# Sheet2.net
KiCad netlist of a schematic drawn in Altium Designer
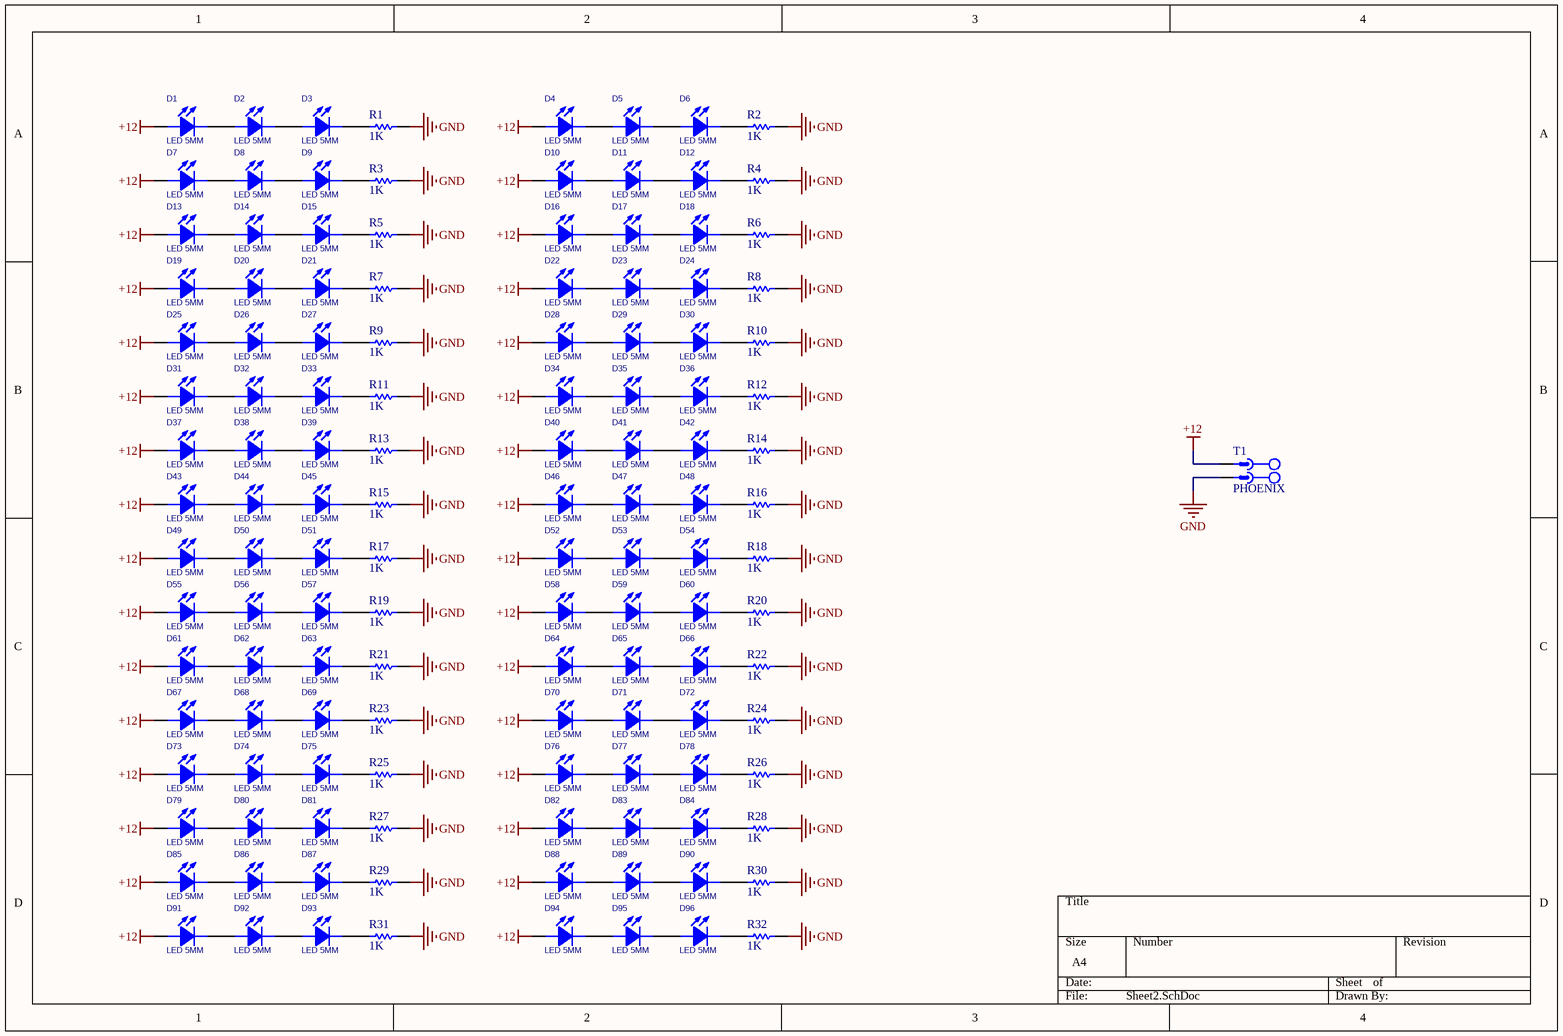
[diagram p0: Sheet2.SchDoc]

(export (version "E")
  (design (tool "Eeschema 10.0.6"))
  (components
    (comp (ref "D1")
      (value "LED 5MM")
      (footprint "LED5MM_BLUE")
      (description "Light Emitting Diode")
      (fields (field (name "DESIGNER") "Abbas Basereh"))
      (libsource (lib "Altium") (part "LED 5MM"))
    )
    (comp (ref "D2")
      (value "LED 5MM")
      (footprint "LED5MM_BLUE")
      (description "Light Emitting Diode")
      (fields (field (name "DESIGNER") "Abbas Basereh"))
      (libsource (lib "Altium") (part "LED 5MM"))
    )
    (comp (ref "D3")
      (value "LED 5MM")
      (footprint "LED5MM_BLUE")
      (description "Light Emitting Diode")
      (fields (field (name "DESIGNER") "Abbas Basereh"))
      (libsource (lib "Altium") (part "LED 5MM"))
    )
    (comp (ref "D4")
      (value "LED 5MM")
      (footprint "LED5MM_BLUE")
      (description "Light Emitting Diode")
      (fields (field (name "DESIGNER") "Abbas Basereh"))
      (libsource (lib "Altium") (part "LED 5MM"))
    )
    (comp (ref "D5")
      (value "LED 5MM")
      (footprint "LED5MM_BLUE")
      (description "Light Emitting Diode")
      (fields (field (name "DESIGNER") "Abbas Basereh"))
      (libsource (lib "Altium") (part "LED 5MM"))
    )
    (comp (ref "D6")
      (value "LED 5MM")
      (footprint "LED5MM_BLUE")
      (description "Light Emitting Diode")
      (fields (field (name "DESIGNER") "Abbas Basereh"))
      (libsource (lib "Altium") (part "LED 5MM"))
    )
    (comp (ref "D7")
      (value "LED 5MM")
      (footprint "LED5MM_BLUE")
      (description "Light Emitting Diode")
      (fields (field (name "DESIGNER") "Abbas Basereh"))
      (libsource (lib "Altium") (part "LED 5MM"))
    )
    (comp (ref "D8")
      (value "LED 5MM")
      (footprint "LED5MM_BLUE")
      (description "Light Emitting Diode")
      (fields (field (name "DESIGNER") "Abbas Basereh"))
      (libsource (lib "Altium") (part "LED 5MM"))
    )
    (comp (ref "D9")
      (value "LED 5MM")
      (footprint "LED5MM_BLUE")
      (description "Light Emitting Diode")
      (fields (field (name "DESIGNER") "Abbas Basereh"))
      (libsource (lib "Altium") (part "LED 5MM"))
    )
    (comp (ref "D10")
      (value "LED 5MM")
      (footprint "LED5MM_BLUE")
      (description "Light Emitting Diode")
      (fields (field (name "DESIGNER") "Abbas Basereh"))
      (libsource (lib "Altium") (part "LED 5MM"))
    )
    (comp (ref "D11")
      (value "LED 5MM")
      (footprint "LED5MM_BLUE")
      (description "Light Emitting Diode")
      (fields (field (name "DESIGNER") "Abbas Basereh"))
      (libsource (lib "Altium") (part "LED 5MM"))
    )
    (comp (ref "D12")
      (value "LED 5MM")
      (footprint "LED5MM_BLUE")
      (description "Light Emitting Diode")
      (fields (field (name "DESIGNER") "Abbas Basereh"))
      (libsource (lib "Altium") (part "LED 5MM"))
    )
    (comp (ref "D13")
      (value "LED 5MM")
      (footprint "LED5MM_BLUE")
      (description "Light Emitting Diode")
      (fields (field (name "DESIGNER") "Abbas Basereh"))
      (libsource (lib "Altium") (part "LED 5MM"))
    )
    (comp (ref "D14")
      (value "LED 5MM")
      (footprint "LED5MM_BLUE")
      (description "Light Emitting Diode")
      (fields (field (name "DESIGNER") "Abbas Basereh"))
      (libsource (lib "Altium") (part "LED 5MM"))
    )
    (comp (ref "D15")
      (value "LED 5MM")
      (footprint "LED5MM_BLUE")
      (description "Light Emitting Diode")
      (fields (field (name "DESIGNER") "Abbas Basereh"))
      (libsource (lib "Altium") (part "LED 5MM"))
    )
    (comp (ref "D16")
      (value "LED 5MM")
      (footprint "LED5MM_BLUE")
      (description "Light Emitting Diode")
      (fields (field (name "DESIGNER") "Abbas Basereh"))
      (libsource (lib "Altium") (part "LED 5MM"))
    )
    (comp (ref "D17")
      (value "LED 5MM")
      (footprint "LED5MM_BLUE")
      (description "Light Emitting Diode")
      (fields (field (name "DESIGNER") "Abbas Basereh"))
      (libsource (lib "Altium") (part "LED 5MM"))
    )
    (comp (ref "D18")
      (value "LED 5MM")
      (footprint "LED5MM_BLUE")
      (description "Light Emitting Diode")
      (fields (field (name "DESIGNER") "Abbas Basereh"))
      (libsource (lib "Altium") (part "LED 5MM"))
    )
    (comp (ref "D19")
      (value "LED 5MM")
      (footprint "LED5MM_BLUE")
      (description "Light Emitting Diode")
      (fields (field (name "DESIGNER") "Abbas Basereh"))
      (libsource (lib "Altium") (part "LED 5MM"))
    )
    (comp (ref "D20")
      (value "LED 5MM")
      (footprint "LED5MM_BLUE")
      (description "Light Emitting Diode")
      (fields (field (name "DESIGNER") "Abbas Basereh"))
      (libsource (lib "Altium") (part "LED 5MM"))
    )
    (comp (ref "D21")
      (value "LED 5MM")
      (footprint "LED5MM_BLUE")
      (description "Light Emitting Diode")
      (fields (field (name "DESIGNER") "Abbas Basereh"))
      (libsource (lib "Altium") (part "LED 5MM"))
    )
    (comp (ref "D22")
      (value "LED 5MM")
      (footprint "LED5MM_BLUE")
      (description "Light Emitting Diode")
      (fields (field (name "DESIGNER") "Abbas Basereh"))
      (libsource (lib "Altium") (part "LED 5MM"))
    )
    (comp (ref "D23")
      (value "LED 5MM")
      (footprint "LED5MM_BLUE")
      (description "Light Emitting Diode")
      (fields (field (name "DESIGNER") "Abbas Basereh"))
      (libsource (lib "Altium") (part "LED 5MM"))
    )
    (comp (ref "D24")
      (value "LED 5MM")
      (footprint "LED5MM_BLUE")
      (description "Light Emitting Diode")
      (fields (field (name "DESIGNER") "Abbas Basereh"))
      (libsource (lib "Altium") (part "LED 5MM"))
    )
    (comp (ref "D25")
      (value "LED 5MM")
      (footprint "LED5MM_BLUE")
      (description "Light Emitting Diode")
      (fields (field (name "DESIGNER") "Abbas Basereh"))
      (libsource (lib "Altium") (part "LED 5MM"))
    )
    (comp (ref "D26")
      (value "LED 5MM")
      (footprint "LED5MM_BLUE")
      (description "Light Emitting Diode")
      (fields (field (name "DESIGNER") "Abbas Basereh"))
      (libsource (lib "Altium") (part "LED 5MM"))
    )
    (comp (ref "D27")
      (value "LED 5MM")
      (footprint "LED5MM_BLUE")
      (description "Light Emitting Diode")
      (fields (field (name "DESIGNER") "Abbas Basereh"))
      (libsource (lib "Altium") (part "LED 5MM"))
    )
    (comp (ref "D28")
      (value "LED 5MM")
      (footprint "LED5MM_BLUE")
      (description "Light Emitting Diode")
      (fields (field (name "DESIGNER") "Abbas Basereh"))
      (libsource (lib "Altium") (part "LED 5MM"))
    )
    (comp (ref "D29")
      (value "LED 5MM")
      (footprint "LED5MM_BLUE")
      (description "Light Emitting Diode")
      (fields (field (name "DESIGNER") "Abbas Basereh"))
      (libsource (lib "Altium") (part "LED 5MM"))
    )
    (comp (ref "D30")
      (value "LED 5MM")
      (footprint "LED5MM_BLUE")
      (description "Light Emitting Diode")
      (fields (field (name "DESIGNER") "Abbas Basereh"))
      (libsource (lib "Altium") (part "LED 5MM"))
    )
    (comp (ref "D31")
      (value "LED 5MM")
      (footprint "LED5MM_BLUE")
      (description "Light Emitting Diode")
      (fields (field (name "DESIGNER") "Abbas Basereh"))
      (libsource (lib "Altium") (part "LED 5MM"))
    )
    (comp (ref "D32")
      (value "LED 5MM")
      (footprint "LED5MM_BLUE")
      (description "Light Emitting Diode")
      (fields (field (name "DESIGNER") "Abbas Basereh"))
      (libsource (lib "Altium") (part "LED 5MM"))
    )
    (comp (ref "D33")
      (value "LED 5MM")
      (footprint "LED5MM_BLUE")
      (description "Light Emitting Diode")
      (fields (field (name "DESIGNER") "Abbas Basereh"))
      (libsource (lib "Altium") (part "LED 5MM"))
    )
    (comp (ref "D34")
      (value "LED 5MM")
      (footprint "LED5MM_BLUE")
      (description "Light Emitting Diode")
      (fields (field (name "DESIGNER") "Abbas Basereh"))
      (libsource (lib "Altium") (part "LED 5MM"))
    )
    (comp (ref "D35")
      (value "LED 5MM")
      (footprint "LED5MM_BLUE")
      (description "Light Emitting Diode")
      (fields (field (name "DESIGNER") "Abbas Basereh"))
      (libsource (lib "Altium") (part "LED 5MM"))
    )
    (comp (ref "D36")
      (value "LED 5MM")
      (footprint "LED5MM_BLUE")
      (description "Light Emitting Diode")
      (fields (field (name "DESIGNER") "Abbas Basereh"))
      (libsource (lib "Altium") (part "LED 5MM"))
    )
    (comp (ref "D37")
      (value "LED 5MM")
      (footprint "LED5MM_BLUE")
      (description "Light Emitting Diode")
      (fields (field (name "DESIGNER") "Abbas Basereh"))
      (libsource (lib "Altium") (part "LED 5MM"))
    )
    (comp (ref "D38")
      (value "LED 5MM")
      (footprint "LED5MM_BLUE")
      (description "Light Emitting Diode")
      (fields (field (name "DESIGNER") "Abbas Basereh"))
      (libsource (lib "Altium") (part "LED 5MM"))
    )
    (comp (ref "D39")
      (value "LED 5MM")
      (footprint "LED5MM_BLUE")
      (description "Light Emitting Diode")
      (fields (field (name "DESIGNER") "Abbas Basereh"))
      (libsource (lib "Altium") (part "LED 5MM"))
    )
    (comp (ref "D40")
      (value "LED 5MM")
      (footprint "LED5MM_BLUE")
      (description "Light Emitting Diode")
      (fields (field (name "DESIGNER") "Abbas Basereh"))
      (libsource (lib "Altium") (part "LED 5MM"))
    )
    (comp (ref "D41")
      (value "LED 5MM")
      (footprint "LED5MM_BLUE")
      (description "Light Emitting Diode")
      (fields (field (name "DESIGNER") "Abbas Basereh"))
      (libsource (lib "Altium") (part "LED 5MM"))
    )
    (comp (ref "D42")
      (value "LED 5MM")
      (footprint "LED5MM_BLUE")
      (description "Light Emitting Diode")
      (fields (field (name "DESIGNER") "Abbas Basereh"))
      (libsource (lib "Altium") (part "LED 5MM"))
    )
    (comp (ref "D43")
      (value "LED 5MM")
      (footprint "LED5MM_BLUE")
      (description "Light Emitting Diode")
      (fields (field (name "DESIGNER") "Abbas Basereh"))
      (libsource (lib "Altium") (part "LED 5MM"))
    )
    (comp (ref "D44")
      (value "LED 5MM")
      (footprint "LED5MM_BLUE")
      (description "Light Emitting Diode")
      (fields (field (name "DESIGNER") "Abbas Basereh"))
      (libsource (lib "Altium") (part "LED 5MM"))
    )
    (comp (ref "D45")
      (value "LED 5MM")
      (footprint "LED5MM_BLUE")
      (description "Light Emitting Diode")
      (fields (field (name "DESIGNER") "Abbas Basereh"))
      (libsource (lib "Altium") (part "LED 5MM"))
    )
    (comp (ref "D46")
      (value "LED 5MM")
      (footprint "LED5MM_BLUE")
      (description "Light Emitting Diode")
      (fields (field (name "DESIGNER") "Abbas Basereh"))
      (libsource (lib "Altium") (part "LED 5MM"))
    )
    (comp (ref "D47")
      (value "LED 5MM")
      (footprint "LED5MM_BLUE")
      (description "Light Emitting Diode")
      (fields (field (name "DESIGNER") "Abbas Basereh"))
      (libsource (lib "Altium") (part "LED 5MM"))
    )
    (comp (ref "D48")
      (value "LED 5MM")
      (footprint "LED5MM_BLUE")
      (description "Light Emitting Diode")
      (fields (field (name "DESIGNER") "Abbas Basereh"))
      (libsource (lib "Altium") (part "LED 5MM"))
    )
    (comp (ref "D49")
      (value "LED 5MM")
      (footprint "LED5MM_BLUE")
      (description "Light Emitting Diode")
      (fields (field (name "DESIGNER") "Abbas Basereh"))
      (libsource (lib "Altium") (part "LED 5MM"))
    )
    (comp (ref "D50")
      (value "LED 5MM")
      (footprint "LED5MM_BLUE")
      (description "Light Emitting Diode")
      (fields (field (name "DESIGNER") "Abbas Basereh"))
      (libsource (lib "Altium") (part "LED 5MM"))
    )
    (comp (ref "D51")
      (value "LED 5MM")
      (footprint "LED5MM_BLUE")
      (description "Light Emitting Diode")
      (fields (field (name "DESIGNER") "Abbas Basereh"))
      (libsource (lib "Altium") (part "LED 5MM"))
    )
    (comp (ref "D52")
      (value "LED 5MM")
      (footprint "LED5MM_BLUE")
      (description "Light Emitting Diode")
      (fields (field (name "DESIGNER") "Abbas Basereh"))
      (libsource (lib "Altium") (part "LED 5MM"))
    )
    (comp (ref "D53")
      (value "LED 5MM")
      (footprint "LED5MM_BLUE")
      (description "Light Emitting Diode")
      (fields (field (name "DESIGNER") "Abbas Basereh"))
      (libsource (lib "Altium") (part "LED 5MM"))
    )
    (comp (ref "D54")
      (value "LED 5MM")
      (footprint "LED5MM_BLUE")
      (description "Light Emitting Diode")
      (fields (field (name "DESIGNER") "Abbas Basereh"))
      (libsource (lib "Altium") (part "LED 5MM"))
    )
    (comp (ref "D55")
      (value "LED 5MM")
      (footprint "LED5MM_BLUE")
      (description "Light Emitting Diode")
      (fields (field (name "DESIGNER") "Abbas Basereh"))
      (libsource (lib "Altium") (part "LED 5MM"))
    )
    (comp (ref "D56")
      (value "LED 5MM")
      (footprint "LED5MM_BLUE")
      (description "Light Emitting Diode")
      (fields (field (name "DESIGNER") "Abbas Basereh"))
      (libsource (lib "Altium") (part "LED 5MM"))
    )
    (comp (ref "D57")
      (value "LED 5MM")
      (footprint "LED5MM_BLUE")
      (description "Light Emitting Diode")
      (fields (field (name "DESIGNER") "Abbas Basereh"))
      (libsource (lib "Altium") (part "LED 5MM"))
    )
    (comp (ref "D58")
      (value "LED 5MM")
      (footprint "LED5MM_BLUE")
      (description "Light Emitting Diode")
      (fields (field (name "DESIGNER") "Abbas Basereh"))
      (libsource (lib "Altium") (part "LED 5MM"))
    )
    (comp (ref "D59")
      (value "LED 5MM")
      (footprint "LED5MM_BLUE")
      (description "Light Emitting Diode")
      (fields (field (name "DESIGNER") "Abbas Basereh"))
      (libsource (lib "Altium") (part "LED 5MM"))
    )
    (comp (ref "D60")
      (value "LED 5MM")
      (footprint "LED5MM_BLUE")
      (description "Light Emitting Diode")
      (fields (field (name "DESIGNER") "Abbas Basereh"))
      (libsource (lib "Altium") (part "LED 5MM"))
    )
    (comp (ref "D61")
      (value "LED 5MM")
      (footprint "LED5MM_BLUE")
      (description "Light Emitting Diode")
      (fields (field (name "DESIGNER") "Abbas Basereh"))
      (libsource (lib "Altium") (part "LED 5MM"))
    )
    (comp (ref "D62")
      (value "LED 5MM")
      (footprint "LED5MM_BLUE")
      (description "Light Emitting Diode")
      (fields (field (name "DESIGNER") "Abbas Basereh"))
      (libsource (lib "Altium") (part "LED 5MM"))
    )
    (comp (ref "D63")
      (value "LED 5MM")
      (footprint "LED5MM_BLUE")
      (description "Light Emitting Diode")
      (fields (field (name "DESIGNER") "Abbas Basereh"))
      (libsource (lib "Altium") (part "LED 5MM"))
    )
    (comp (ref "D64")
      (value "LED 5MM")
      (footprint "LED5MM_BLUE")
      (description "Light Emitting Diode")
      (fields (field (name "DESIGNER") "Abbas Basereh"))
      (libsource (lib "Altium") (part "LED 5MM"))
    )
    (comp (ref "D65")
      (value "LED 5MM")
      (footprint "LED5MM_BLUE")
      (description "Light Emitting Diode")
      (fields (field (name "DESIGNER") "Abbas Basereh"))
      (libsource (lib "Altium") (part "LED 5MM"))
    )
    (comp (ref "D66")
      (value "LED 5MM")
      (footprint "LED5MM_BLUE")
      (description "Light Emitting Diode")
      (fields (field (name "DESIGNER") "Abbas Basereh"))
      (libsource (lib "Altium") (part "LED 5MM"))
    )
    (comp (ref "D67")
      (value "LED 5MM")
      (footprint "LED5MM_BLUE")
      (description "Light Emitting Diode")
      (fields (field (name "DESIGNER") "Abbas Basereh"))
      (libsource (lib "Altium") (part "LED 5MM"))
    )
    (comp (ref "D68")
      (value "LED 5MM")
      (footprint "LED5MM_BLUE")
      (description "Light Emitting Diode")
      (fields (field (name "DESIGNER") "Abbas Basereh"))
      (libsource (lib "Altium") (part "LED 5MM"))
    )
    (comp (ref "D69")
      (value "LED 5MM")
      (footprint "LED5MM_BLUE")
      (description "Light Emitting Diode")
      (fields (field (name "DESIGNER") "Abbas Basereh"))
      (libsource (lib "Altium") (part "LED 5MM"))
    )
    (comp (ref "D70")
      (value "LED 5MM")
      (footprint "LED5MM_BLUE")
      (description "Light Emitting Diode")
      (fields (field (name "DESIGNER") "Abbas Basereh"))
      (libsource (lib "Altium") (part "LED 5MM"))
    )
    (comp (ref "D71")
      (value "LED 5MM")
      (footprint "LED5MM_BLUE")
      (description "Light Emitting Diode")
      (fields (field (name "DESIGNER") "Abbas Basereh"))
      (libsource (lib "Altium") (part "LED 5MM"))
    )
    (comp (ref "D72")
      (value "LED 5MM")
      (footprint "LED5MM_BLUE")
      (description "Light Emitting Diode")
      (fields (field (name "DESIGNER") "Abbas Basereh"))
      (libsource (lib "Altium") (part "LED 5MM"))
    )
    (comp (ref "D73")
      (value "LED 5MM")
      (footprint "LED5MM_BLUE")
      (description "Light Emitting Diode")
      (fields (field (name "DESIGNER") "Abbas Basereh"))
      (libsource (lib "Altium") (part "LED 5MM"))
    )
    (comp (ref "D74")
      (value "LED 5MM")
      (footprint "LED5MM_BLUE")
      (description "Light Emitting Diode")
      (fields (field (name "DESIGNER") "Abbas Basereh"))
      (libsource (lib "Altium") (part "LED 5MM"))
    )
    (comp (ref "D75")
      (value "LED 5MM")
      (footprint "LED5MM_BLUE")
      (description "Light Emitting Diode")
      (fields (field (name "DESIGNER") "Abbas Basereh"))
      (libsource (lib "Altium") (part "LED 5MM"))
    )
    (comp (ref "D76")
      (value "LED 5MM")
      (footprint "LED5MM_BLUE")
      (description "Light Emitting Diode")
      (fields (field (name "DESIGNER") "Abbas Basereh"))
      (libsource (lib "Altium") (part "LED 5MM"))
    )
    (comp (ref "D77")
      (value "LED 5MM")
      (footprint "LED5MM_BLUE")
      (description "Light Emitting Diode")
      (fields (field (name "DESIGNER") "Abbas Basereh"))
      (libsource (lib "Altium") (part "LED 5MM"))
    )
    (comp (ref "D78")
      (value "LED 5MM")
      (footprint "LED5MM_BLUE")
      (description "Light Emitting Diode")
      (fields (field (name "DESIGNER") "Abbas Basereh"))
      (libsource (lib "Altium") (part "LED 5MM"))
    )
    (comp (ref "D79")
      (value "LED 5MM")
      (footprint "LED5MM_BLUE")
      (description "Light Emitting Diode")
      (fields (field (name "DESIGNER") "Abbas Basereh"))
      (libsource (lib "Altium") (part "LED 5MM"))
    )
    (comp (ref "D80")
      (value "LED 5MM")
      (footprint "LED5MM_BLUE")
      (description "Light Emitting Diode")
      (fields (field (name "DESIGNER") "Abbas Basereh"))
      (libsource (lib "Altium") (part "LED 5MM"))
    )
    (comp (ref "D81")
      (value "LED 5MM")
      (footprint "LED5MM_BLUE")
      (description "Light Emitting Diode")
      (fields (field (name "DESIGNER") "Abbas Basereh"))
      (libsource (lib "Altium") (part "LED 5MM"))
    )
    (comp (ref "D82")
      (value "LED 5MM")
      (footprint "LED5MM_BLUE")
      (description "Light Emitting Diode")
      (fields (field (name "DESIGNER") "Abbas Basereh"))
      (libsource (lib "Altium") (part "LED 5MM"))
    )
    (comp (ref "D83")
      (value "LED 5MM")
      (footprint "LED5MM_BLUE")
      (description "Light Emitting Diode")
      (fields (field (name "DESIGNER") "Abbas Basereh"))
      (libsource (lib "Altium") (part "LED 5MM"))
    )
    (comp (ref "D84")
      (value "LED 5MM")
      (footprint "LED5MM_BLUE")
      (description "Light Emitting Diode")
      (fields (field (name "DESIGNER") "Abbas Basereh"))
      (libsource (lib "Altium") (part "LED 5MM"))
    )
    (comp (ref "D85")
      (value "LED 5MM")
      (footprint "LED5MM_BLUE")
      (description "Light Emitting Diode")
      (fields (field (name "DESIGNER") "Abbas Basereh"))
      (libsource (lib "Altium") (part "LED 5MM"))
    )
    (comp (ref "D86")
      (value "LED 5MM")
      (footprint "LED5MM_BLUE")
      (description "Light Emitting Diode")
      (fields (field (name "DESIGNER") "Abbas Basereh"))
      (libsource (lib "Altium") (part "LED 5MM"))
    )
    (comp (ref "D87")
      (value "LED 5MM")
      (footprint "LED5MM_BLUE")
      (description "Light Emitting Diode")
      (fields (field (name "DESIGNER") "Abbas Basereh"))
      (libsource (lib "Altium") (part "LED 5MM"))
    )
    (comp (ref "D88")
      (value "LED 5MM")
      (footprint "LED5MM_BLUE")
      (description "Light Emitting Diode")
      (fields (field (name "DESIGNER") "Abbas Basereh"))
      (libsource (lib "Altium") (part "LED 5MM"))
    )
    (comp (ref "D89")
      (value "LED 5MM")
      (footprint "LED5MM_BLUE")
      (description "Light Emitting Diode")
      (fields (field (name "DESIGNER") "Abbas Basereh"))
      (libsource (lib "Altium") (part "LED 5MM"))
    )
    (comp (ref "D90")
      (value "LED 5MM")
      (footprint "LED5MM_BLUE")
      (description "Light Emitting Diode")
      (fields (field (name "DESIGNER") "Abbas Basereh"))
      (libsource (lib "Altium") (part "LED 5MM"))
    )
    (comp (ref "D91")
      (value "LED 5MM")
      (footprint "LED5MM_BLUE")
      (description "Light Emitting Diode")
      (fields (field (name "DESIGNER") "Abbas Basereh"))
      (libsource (lib "Altium") (part "LED 5MM"))
    )
    (comp (ref "D92")
      (value "LED 5MM")
      (footprint "LED5MM_BLUE")
      (description "Light Emitting Diode")
      (fields (field (name "DESIGNER") "Abbas Basereh"))
      (libsource (lib "Altium") (part "LED 5MM"))
    )
    (comp (ref "D93")
      (value "LED 5MM")
      (footprint "LED5MM_BLUE")
      (description "Light Emitting Diode")
      (fields (field (name "DESIGNER") "Abbas Basereh"))
      (libsource (lib "Altium") (part "LED 5MM"))
    )
    (comp (ref "D94")
      (value "LED 5MM")
      (footprint "LED5MM_BLUE")
      (description "Light Emitting Diode")
      (fields (field (name "DESIGNER") "Abbas Basereh"))
      (libsource (lib "Altium") (part "LED 5MM"))
    )
    (comp (ref "D95")
      (value "LED 5MM")
      (footprint "LED5MM_BLUE")
      (description "Light Emitting Diode")
      (fields (field (name "DESIGNER") "Abbas Basereh"))
      (libsource (lib "Altium") (part "LED 5MM"))
    )
    (comp (ref "D96")
      (value "LED 5MM")
      (footprint "LED5MM_BLUE")
      (description "Light Emitting Diode")
      (fields (field (name "DESIGNER") "Abbas Basereh"))
      (libsource (lib "Altium") (part "LED 5MM"))
    )
    (comp (ref "R1")
      (value "1K")
      (footprint "Axial 0_25 W, 0_4 IN LEAD PITCH")
      (description "RES Axial 0.25W")
      (fields (field (name "DESIGNER") "Abbas Basereh"))
      (libsource (lib "Altium") (part "RES Axial 0.25W"))
    )
    (comp (ref "R2")
      (value "1K")
      (footprint "Axial 0_25 W, 0_4 IN LEAD PITCH")
      (description "RES Axial 0.25W")
      (fields (field (name "DESIGNER") "Abbas Basereh"))
      (libsource (lib "Altium") (part "RES Axial 0.25W"))
    )
    (comp (ref "R3")
      (value "1K")
      (footprint "Axial 0_25 W, 0_4 IN LEAD PITCH")
      (description "RES Axial 0.25W")
      (fields (field (name "DESIGNER") "Abbas Basereh"))
      (libsource (lib "Altium") (part "RES Axial 0.25W"))
    )
    (comp (ref "R4")
      (value "1K")
      (footprint "Axial 0_25 W, 0_4 IN LEAD PITCH")
      (description "RES Axial 0.25W")
      (fields (field (name "DESIGNER") "Abbas Basereh"))
      (libsource (lib "Altium") (part "RES Axial 0.25W"))
    )
    (comp (ref "R5")
      (value "1K")
      (footprint "Axial 0_25 W, 0_4 IN LEAD PITCH")
      (description "RES Axial 0.25W")
      (fields (field (name "DESIGNER") "Abbas Basereh"))
      (libsource (lib "Altium") (part "RES Axial 0.25W"))
    )
    (comp (ref "R6")
      (value "1K")
      (footprint "Axial 0_25 W, 0_4 IN LEAD PITCH")
      (description "RES Axial 0.25W")
      (fields (field (name "DESIGNER") "Abbas Basereh"))
      (libsource (lib "Altium") (part "RES Axial 0.25W"))
    )
    (comp (ref "R7")
      (value "1K")
      (footprint "Axial 0_25 W, 0_4 IN LEAD PITCH")
      (description "RES Axial 0.25W")
      (fields (field (name "DESIGNER") "Abbas Basereh"))
      (libsource (lib "Altium") (part "RES Axial 0.25W"))
    )
    (comp (ref "R8")
      (value "1K")
      (footprint "Axial 0_25 W, 0_4 IN LEAD PITCH")
      (description "RES Axial 0.25W")
      (fields (field (name "DESIGNER") "Abbas Basereh"))
      (libsource (lib "Altium") (part "RES Axial 0.25W"))
    )
    (comp (ref "R9")
      (value "1K")
      (footprint "Axial 0_25 W, 0_4 IN LEAD PITCH")
      (description "RES Axial 0.25W")
      (fields (field (name "DESIGNER") "Abbas Basereh"))
      (libsource (lib "Altium") (part "RES Axial 0.25W"))
    )
    (comp (ref "R10")
      (value "1K")
      (footprint "Axial 0_25 W, 0_4 IN LEAD PITCH")
      (description "RES Axial 0.25W")
      (fields (field (name "DESIGNER") "Abbas Basereh"))
      (libsource (lib "Altium") (part "RES Axial 0.25W"))
    )
    (comp (ref "R11")
      (value "1K")
      (footprint "Axial 0_25 W, 0_4 IN LEAD PITCH")
      (description "RES Axial 0.25W")
      (fields (field (name "DESIGNER") "Abbas Basereh"))
      (libsource (lib "Altium") (part "RES Axial 0.25W"))
    )
    (comp (ref "R12")
      (value "1K")
      (footprint "Axial 0_25 W, 0_4 IN LEAD PITCH")
      (description "RES Axial 0.25W")
      (fields (field (name "DESIGNER") "Abbas Basereh"))
      (libsource (lib "Altium") (part "RES Axial 0.25W"))
    )
    (comp (ref "R13")
      (value "1K")
      (footprint "Axial 0_25 W, 0_4 IN LEAD PITCH")
      (description "RES Axial 0.25W")
      (fields (field (name "DESIGNER") "Abbas Basereh"))
      (libsource (lib "Altium") (part "RES Axial 0.25W"))
    )
    (comp (ref "R14")
      (value "1K")
      (footprint "Axial 0_25 W, 0_4 IN LEAD PITCH")
      (description "RES Axial 0.25W")
      (fields (field (name "DESIGNER") "Abbas Basereh"))
      (libsource (lib "Altium") (part "RES Axial 0.25W"))
    )
    (comp (ref "R15")
      (value "1K")
      (footprint "Axial 0_25 W, 0_4 IN LEAD PITCH")
      (description "RES Axial 0.25W")
      (fields (field (name "DESIGNER") "Abbas Basereh"))
      (libsource (lib "Altium") (part "RES Axial 0.25W"))
    )
    (comp (ref "R16")
      (value "1K")
      (footprint "Axial 0_25 W, 0_4 IN LEAD PITCH")
      (description "RES Axial 0.25W")
      (fields (field (name "DESIGNER") "Abbas Basereh"))
      (libsource (lib "Altium") (part "RES Axial 0.25W"))
    )
    (comp (ref "R17")
      (value "1K")
      (footprint "Axial 0_25 W, 0_4 IN LEAD PITCH")
      (description "RES Axial 0.25W")
      (fields (field (name "DESIGNER") "Abbas Basereh"))
      (libsource (lib "Altium") (part "RES Axial 0.25W"))
    )
    (comp (ref "R18")
      (value "1K")
      (footprint "Axial 0_25 W, 0_4 IN LEAD PITCH")
      (description "RES Axial 0.25W")
      (fields (field (name "DESIGNER") "Abbas Basereh"))
      (libsource (lib "Altium") (part "RES Axial 0.25W"))
    )
    (comp (ref "R19")
      (value "1K")
      (footprint "Axial 0_25 W, 0_4 IN LEAD PITCH")
      (description "RES Axial 0.25W")
      (fields (field (name "DESIGNER") "Abbas Basereh"))
      (libsource (lib "Altium") (part "RES Axial 0.25W"))
    )
    (comp (ref "R20")
      (value "1K")
      (footprint "Axial 0_25 W, 0_4 IN LEAD PITCH")
      (description "RES Axial 0.25W")
      (fields (field (name "DESIGNER") "Abbas Basereh"))
      (libsource (lib "Altium") (part "RES Axial 0.25W"))
    )
    (comp (ref "R21")
      (value "1K")
      (footprint "Axial 0_25 W, 0_4 IN LEAD PITCH")
      (description "RES Axial 0.25W")
      (fields (field (name "DESIGNER") "Abbas Basereh"))
      (libsource (lib "Altium") (part "RES Axial 0.25W"))
    )
    (comp (ref "R22")
      (value "1K")
      (footprint "Axial 0_25 W, 0_4 IN LEAD PITCH")
      (description "RES Axial 0.25W")
      (fields (field (name "DESIGNER") "Abbas Basereh"))
      (libsource (lib "Altium") (part "RES Axial 0.25W"))
    )
    (comp (ref "R23")
      (value "1K")
      (footprint "Axial 0_25 W, 0_4 IN LEAD PITCH")
      (description "RES Axial 0.25W")
      (fields (field (name "DESIGNER") "Abbas Basereh"))
      (libsource (lib "Altium") (part "RES Axial 0.25W"))
    )
    (comp (ref "R24")
      (value "1K")
      (footprint "Axial 0_25 W, 0_4 IN LEAD PITCH")
      (description "RES Axial 0.25W")
      (fields (field (name "DESIGNER") "Abbas Basereh"))
      (libsource (lib "Altium") (part "RES Axial 0.25W"))
    )
    (comp (ref "R25")
      (value "1K")
      (footprint "Axial 0_25 W, 0_4 IN LEAD PITCH")
      (description "RES Axial 0.25W")
      (fields (field (name "DESIGNER") "Abbas Basereh"))
      (libsource (lib "Altium") (part "RES Axial 0.25W"))
    )
    (comp (ref "R26")
      (value "1K")
      (footprint "Axial 0_25 W, 0_4 IN LEAD PITCH")
      (description "RES Axial 0.25W")
      (fields (field (name "DESIGNER") "Abbas Basereh"))
      (libsource (lib "Altium") (part "RES Axial 0.25W"))
    )
    (comp (ref "R27")
      (value "1K")
      (footprint "Axial 0_25 W, 0_4 IN LEAD PITCH")
      (description "RES Axial 0.25W")
      (fields (field (name "DESIGNER") "Abbas Basereh"))
      (libsource (lib "Altium") (part "RES Axial 0.25W"))
    )
    (comp (ref "R28")
      (value "1K")
      (footprint "Axial 0_25 W, 0_4 IN LEAD PITCH")
      (description "RES Axial 0.25W")
      (fields (field (name "DESIGNER") "Abbas Basereh"))
      (libsource (lib "Altium") (part "RES Axial 0.25W"))
    )
    (comp (ref "R29")
      (value "1K")
      (footprint "Axial 0_25 W, 0_4 IN LEAD PITCH")
      (description "RES Axial 0.25W")
      (fields (field (name "DESIGNER") "Abbas Basereh"))
      (libsource (lib "Altium") (part "RES Axial 0.25W"))
    )
    (comp (ref "R30")
      (value "1K")
      (footprint "Axial 0_25 W, 0_4 IN LEAD PITCH")
      (description "RES Axial 0.25W")
      (fields (field (name "DESIGNER") "Abbas Basereh"))
      (libsource (lib "Altium") (part "RES Axial 0.25W"))
    )
    (comp (ref "R31")
      (value "1K")
      (footprint "Axial 0_25 W, 0_4 IN LEAD PITCH")
      (description "RES Axial 0.25W")
      (fields (field (name "DESIGNER") "Abbas Basereh"))
      (libsource (lib "Altium") (part "RES Axial 0.25W"))
    )
    (comp (ref "R32")
      (value "1K")
      (footprint "Axial 0_25 W, 0_4 IN LEAD PITCH")
      (description "RES Axial 0.25W")
      (fields (field (name "DESIGNER") "Abbas Basereh"))
      (libsource (lib "Altium") (part "RES Axial 0.25W"))
    )
    (comp (ref "T1")
      (value "PHOENIX")
      (footprint "MSTB 2,5/2-G-5,08")
      (description "2 Pitch: 5.08 mm Color: green Contact surface: Tin Assembly")
      (fields
        (field (name "MANUFACTURER") "PHOENIX CONTACT")
        (field (name "VOLTAGE") "320 V")
        (field (name "DESIGNER") "ABBAS BASEREH")
      )
      (libsource (lib "Altium") (part "CON_Phoenix_MSTB_02"))
    )
  )
  (nets
    (net (code "1") (name "+12") (class "Default")
      (node (ref "D1") (pin "1") (pinfunction "ANODE_1") (pintype "passive"))
      (node (ref "D10") (pin "1") (pinfunction "ANODE_1") (pintype "passive"))
      (node (ref "D13") (pin "1") (pinfunction "ANODE_1") (pintype "passive"))
      (node (ref "D16") (pin "1") (pinfunction "ANODE_1") (pintype "passive"))
      (node (ref "D19") (pin "1") (pinfunction "ANODE_1") (pintype "passive"))
      (node (ref "D22") (pin "1") (pinfunction "ANODE_1") (pintype "passive"))
      (node (ref "D25") (pin "1") (pinfunction "ANODE_1") (pintype "passive"))
      (node (ref "D28") (pin "1") (pinfunction "ANODE_1") (pintype "passive"))
      (node (ref "D31") (pin "1") (pinfunction "ANODE_1") (pintype "passive"))
      (node (ref "D34") (pin "1") (pinfunction "ANODE_1") (pintype "passive"))
      (node (ref "D37") (pin "1") (pinfunction "ANODE_1") (pintype "passive"))
      (node (ref "D4") (pin "1") (pinfunction "ANODE_1") (pintype "passive"))
      (node (ref "D40") (pin "1") (pinfunction "ANODE_1") (pintype "passive"))
      (node (ref "D43") (pin "1") (pinfunction "ANODE_1") (pintype "passive"))
      (node (ref "D46") (pin "1") (pinfunction "ANODE_1") (pintype "passive"))
      (node (ref "D49") (pin "1") (pinfunction "ANODE_1") (pintype "passive"))
      (node (ref "D52") (pin "1") (pinfunction "ANODE_1") (pintype "passive"))
      (node (ref "D55") (pin "1") (pinfunction "ANODE_1") (pintype "passive"))
      (node (ref "D58") (pin "1") (pinfunction "ANODE_1") (pintype "passive"))
      (node (ref "D61") (pin "1") (pinfunction "ANODE_1") (pintype "passive"))
      (node (ref "D64") (pin "1") (pinfunction "ANODE_1") (pintype "passive"))
      (node (ref "D67") (pin "1") (pinfunction "ANODE_1") (pintype "passive"))
      (node (ref "D7") (pin "1") (pinfunction "ANODE_1") (pintype "passive"))
      (node (ref "D70") (pin "1") (pinfunction "ANODE_1") (pintype "passive"))
      (node (ref "D73") (pin "1") (pinfunction "ANODE_1") (pintype "passive"))
      (node (ref "D76") (pin "1") (pinfunction "ANODE_1") (pintype "passive"))
      (node (ref "D79") (pin "1") (pinfunction "ANODE_1") (pintype "passive"))
      (node (ref "D82") (pin "1") (pinfunction "ANODE_1") (pintype "passive"))
      (node (ref "D85") (pin "1") (pinfunction "ANODE_1") (pintype "passive"))
      (node (ref "D88") (pin "1") (pinfunction "ANODE_1") (pintype "passive"))
      (node (ref "D91") (pin "1") (pinfunction "ANODE_1") (pintype "passive"))
      (node (ref "D94") (pin "1") (pinfunction "ANODE_1") (pintype "passive"))
      (node (ref "T1") (pin "1") (pinfunction "1_1") (pintype "passive"))
    )
    (net (code "2") (name "GND") (class "Default")
      (node (ref "R1") (pin "2") (pinfunction "2_2") (pintype "passive"))
      (node (ref "R10") (pin "2") (pinfunction "2_2") (pintype "passive"))
      (node (ref "R11") (pin "2") (pinfunction "2_2") (pintype "passive"))
      (node (ref "R12") (pin "2") (pinfunction "2_2") (pintype "passive"))
      (node (ref "R13") (pin "2") (pinfunction "2_2") (pintype "passive"))
      (node (ref "R14") (pin "2") (pinfunction "2_2") (pintype "passive"))
      (node (ref "R15") (pin "2") (pinfunction "2_2") (pintype "passive"))
      (node (ref "R16") (pin "2") (pinfunction "2_2") (pintype "passive"))
      (node (ref "R17") (pin "2") (pinfunction "2_2") (pintype "passive"))
      (node (ref "R18") (pin "2") (pinfunction "2_2") (pintype "passive"))
      (node (ref "R19") (pin "2") (pinfunction "2_2") (pintype "passive"))
      (node (ref "R2") (pin "2") (pinfunction "2_2") (pintype "passive"))
      (node (ref "R20") (pin "2") (pinfunction "2_2") (pintype "passive"))
      (node (ref "R21") (pin "2") (pinfunction "2_2") (pintype "passive"))
      (node (ref "R22") (pin "2") (pinfunction "2_2") (pintype "passive"))
      (node (ref "R23") (pin "2") (pinfunction "2_2") (pintype "passive"))
      (node (ref "R24") (pin "2") (pinfunction "2_2") (pintype "passive"))
      (node (ref "R25") (pin "2") (pinfunction "2_2") (pintype "passive"))
      (node (ref "R26") (pin "2") (pinfunction "2_2") (pintype "passive"))
      (node (ref "R27") (pin "2") (pinfunction "2_2") (pintype "passive"))
      (node (ref "R28") (pin "2") (pinfunction "2_2") (pintype "passive"))
      (node (ref "R29") (pin "2") (pinfunction "2_2") (pintype "passive"))
      (node (ref "R3") (pin "2") (pinfunction "2_2") (pintype "passive"))
      (node (ref "R30") (pin "2") (pinfunction "2_2") (pintype "passive"))
      (node (ref "R31") (pin "2") (pinfunction "2_2") (pintype "passive"))
      (node (ref "R32") (pin "2") (pinfunction "2_2") (pintype "passive"))
      (node (ref "R4") (pin "2") (pinfunction "2_2") (pintype "passive"))
      (node (ref "R5") (pin "2") (pinfunction "2_2") (pintype "passive"))
      (node (ref "R6") (pin "2") (pinfunction "2_2") (pintype "passive"))
      (node (ref "R7") (pin "2") (pinfunction "2_2") (pintype "passive"))
      (node (ref "R8") (pin "2") (pinfunction "2_2") (pintype "passive"))
      (node (ref "R9") (pin "2") (pinfunction "2_2") (pintype "passive"))
      (node (ref "T1") (pin "2") (pinfunction "2_2") (pintype "passive"))
    )
    (net (code "3") (name "Net-(D1-CATHODE)") (class "Default")
      (node (ref "D1") (pin "2") (pinfunction "CATHODE_2") (pintype "passive"))
      (node (ref "D2") (pin "1") (pinfunction "ANODE_1") (pintype "passive"))
    )
    (net (code "4") (name "Net-(D2-CATHODE)") (class "Default")
      (node (ref "D2") (pin "2") (pinfunction "CATHODE_2") (pintype "passive"))
      (node (ref "D3") (pin "1") (pinfunction "ANODE_1") (pintype "passive"))
    )
    (net (code "5") (name "Net-(D3-CATHODE)") (class "Default")
      (node (ref "D3") (pin "2") (pinfunction "CATHODE_2") (pintype "passive"))
      (node (ref "R1") (pin "1") (pinfunction "1_1") (pintype "passive"))
    )
    (net (code "6") (name "Net-(D4-CATHODE)") (class "Default")
      (node (ref "D4") (pin "2") (pinfunction "CATHODE_2") (pintype "passive"))
      (node (ref "D5") (pin "1") (pinfunction "ANODE_1") (pintype "passive"))
    )
    (net (code "7") (name "Net-(D5-CATHODE)") (class "Default")
      (node (ref "D5") (pin "2") (pinfunction "CATHODE_2") (pintype "passive"))
      (node (ref "D6") (pin "1") (pinfunction "ANODE_1") (pintype "passive"))
    )
    (net (code "8") (name "Net-(D6-CATHODE)") (class "Default")
      (node (ref "D6") (pin "2") (pinfunction "CATHODE_2") (pintype "passive"))
      (node (ref "R2") (pin "1") (pinfunction "1_1") (pintype "passive"))
    )
    (net (code "9") (name "Net-(D7-CATHODE)") (class "Default")
      (node (ref "D7") (pin "2") (pinfunction "CATHODE_2") (pintype "passive"))
      (node (ref "D8") (pin "1") (pinfunction "ANODE_1") (pintype "passive"))
    )
    (net (code "10") (name "Net-(D8-CATHODE)") (class "Default")
      (node (ref "D8") (pin "2") (pinfunction "CATHODE_2") (pintype "passive"))
      (node (ref "D9") (pin "1") (pinfunction "ANODE_1") (pintype "passive"))
    )
    (net (code "11") (name "Net-(D9-CATHODE)") (class "Default")
      (node (ref "D9") (pin "2") (pinfunction "CATHODE_2") (pintype "passive"))
      (node (ref "R3") (pin "1") (pinfunction "1_1") (pintype "passive"))
    )
    (net (code "12") (name "Net-(D10-CATHODE)") (class "Default")
      (node (ref "D10") (pin "2") (pinfunction "CATHODE_2") (pintype "passive"))
      (node (ref "D11") (pin "1") (pinfunction "ANODE_1") (pintype "passive"))
    )
    (net (code "13") (name "Net-(D11-CATHODE)") (class "Default")
      (node (ref "D11") (pin "2") (pinfunction "CATHODE_2") (pintype "passive"))
      (node (ref "D12") (pin "1") (pinfunction "ANODE_1") (pintype "passive"))
    )
    (net (code "14") (name "Net-(D12-CATHODE)") (class "Default")
      (node (ref "D12") (pin "2") (pinfunction "CATHODE_2") (pintype "passive"))
      (node (ref "R4") (pin "1") (pinfunction "1_1") (pintype "passive"))
    )
    (net (code "15") (name "Net-(D13-CATHODE)") (class "Default")
      (node (ref "D13") (pin "2") (pinfunction "CATHODE_2") (pintype "passive"))
      (node (ref "D14") (pin "1") (pinfunction "ANODE_1") (pintype "passive"))
    )
    (net (code "16") (name "Net-(D14-CATHODE)") (class "Default")
      (node (ref "D14") (pin "2") (pinfunction "CATHODE_2") (pintype "passive"))
      (node (ref "D15") (pin "1") (pinfunction "ANODE_1") (pintype "passive"))
    )
    (net (code "17") (name "Net-(D15-CATHODE)") (class "Default")
      (node (ref "D15") (pin "2") (pinfunction "CATHODE_2") (pintype "passive"))
      (node (ref "R5") (pin "1") (pinfunction "1_1") (pintype "passive"))
    )
    (net (code "18") (name "Net-(D16-CATHODE)") (class "Default")
      (node (ref "D16") (pin "2") (pinfunction "CATHODE_2") (pintype "passive"))
      (node (ref "D17") (pin "1") (pinfunction "ANODE_1") (pintype "passive"))
    )
    (net (code "19") (name "Net-(D17-CATHODE)") (class "Default")
      (node (ref "D17") (pin "2") (pinfunction "CATHODE_2") (pintype "passive"))
      (node (ref "D18") (pin "1") (pinfunction "ANODE_1") (pintype "passive"))
    )
    (net (code "20") (name "Net-(D18-CATHODE)") (class "Default")
      (node (ref "D18") (pin "2") (pinfunction "CATHODE_2") (pintype "passive"))
      (node (ref "R6") (pin "1") (pinfunction "1_1") (pintype "passive"))
    )
    (net (code "21") (name "Net-(D19-CATHODE)") (class "Default")
      (node (ref "D19") (pin "2") (pinfunction "CATHODE_2") (pintype "passive"))
      (node (ref "D20") (pin "1") (pinfunction "ANODE_1") (pintype "passive"))
    )
    (net (code "22") (name "Net-(D20-CATHODE)") (class "Default")
      (node (ref "D20") (pin "2") (pinfunction "CATHODE_2") (pintype "passive"))
      (node (ref "D21") (pin "1") (pinfunction "ANODE_1") (pintype "passive"))
    )
    (net (code "23") (name "Net-(D21-CATHODE)") (class "Default")
      (node (ref "D21") (pin "2") (pinfunction "CATHODE_2") (pintype "passive"))
      (node (ref "R7") (pin "1") (pinfunction "1_1") (pintype "passive"))
    )
    (net (code "24") (name "Net-(D22-CATHODE)") (class "Default")
      (node (ref "D22") (pin "2") (pinfunction "CATHODE_2") (pintype "passive"))
      (node (ref "D23") (pin "1") (pinfunction "ANODE_1") (pintype "passive"))
    )
    (net (code "25") (name "Net-(D23-CATHODE)") (class "Default")
      (node (ref "D23") (pin "2") (pinfunction "CATHODE_2") (pintype "passive"))
      (node (ref "D24") (pin "1") (pinfunction "ANODE_1") (pintype "passive"))
    )
    (net (code "26") (name "Net-(D24-CATHODE)") (class "Default")
      (node (ref "D24") (pin "2") (pinfunction "CATHODE_2") (pintype "passive"))
      (node (ref "R8") (pin "1") (pinfunction "1_1") (pintype "passive"))
    )
    (net (code "27") (name "Net-(D25-CATHODE)") (class "Default")
      (node (ref "D25") (pin "2") (pinfunction "CATHODE_2") (pintype "passive"))
      (node (ref "D26") (pin "1") (pinfunction "ANODE_1") (pintype "passive"))
    )
    (net (code "28") (name "Net-(D26-CATHODE)") (class "Default")
      (node (ref "D26") (pin "2") (pinfunction "CATHODE_2") (pintype "passive"))
      (node (ref "D27") (pin "1") (pinfunction "ANODE_1") (pintype "passive"))
    )
    (net (code "29") (name "Net-(D27-CATHODE)") (class "Default")
      (node (ref "D27") (pin "2") (pinfunction "CATHODE_2") (pintype "passive"))
      (node (ref "R9") (pin "1") (pinfunction "1_1") (pintype "passive"))
    )
    (net (code "30") (name "Net-(D28-CATHODE)") (class "Default")
      (node (ref "D28") (pin "2") (pinfunction "CATHODE_2") (pintype "passive"))
      (node (ref "D29") (pin "1") (pinfunction "ANODE_1") (pintype "passive"))
    )
    (net (code "31") (name "Net-(D29-CATHODE)") (class "Default")
      (node (ref "D29") (pin "2") (pinfunction "CATHODE_2") (pintype "passive"))
      (node (ref "D30") (pin "1") (pinfunction "ANODE_1") (pintype "passive"))
    )
    (net (code "32") (name "Net-(D30-CATHODE)") (class "Default")
      (node (ref "D30") (pin "2") (pinfunction "CATHODE_2") (pintype "passive"))
      (node (ref "R10") (pin "1") (pinfunction "1_1") (pintype "passive"))
    )
    (net (code "33") (name "Net-(D31-CATHODE)") (class "Default")
      (node (ref "D31") (pin "2") (pinfunction "CATHODE_2") (pintype "passive"))
      (node (ref "D32") (pin "1") (pinfunction "ANODE_1") (pintype "passive"))
    )
    (net (code "34") (name "Net-(D32-CATHODE)") (class "Default")
      (node (ref "D32") (pin "2") (pinfunction "CATHODE_2") (pintype "passive"))
      (node (ref "D33") (pin "1") (pinfunction "ANODE_1") (pintype "passive"))
    )
    (net (code "35") (name "Net-(D33-CATHODE)") (class "Default")
      (node (ref "D33") (pin "2") (pinfunction "CATHODE_2") (pintype "passive"))
      (node (ref "R11") (pin "1") (pinfunction "1_1") (pintype "passive"))
    )
    (net (code "36") (name "Net-(D34-CATHODE)") (class "Default")
      (node (ref "D34") (pin "2") (pinfunction "CATHODE_2") (pintype "passive"))
      (node (ref "D35") (pin "1") (pinfunction "ANODE_1") (pintype "passive"))
    )
    (net (code "37") (name "Net-(D35-CATHODE)") (class "Default")
      (node (ref "D35") (pin "2") (pinfunction "CATHODE_2") (pintype "passive"))
      (node (ref "D36") (pin "1") (pinfunction "ANODE_1") (pintype "passive"))
    )
    (net (code "38") (name "Net-(D36-CATHODE)") (class "Default")
      (node (ref "D36") (pin "2") (pinfunction "CATHODE_2") (pintype "passive"))
      (node (ref "R12") (pin "1") (pinfunction "1_1") (pintype "passive"))
    )
    (net (code "39") (name "Net-(D37-CATHODE)") (class "Default")
      (node (ref "D37") (pin "2") (pinfunction "CATHODE_2") (pintype "passive"))
      (node (ref "D38") (pin "1") (pinfunction "ANODE_1") (pintype "passive"))
    )
    (net (code "40") (name "Net-(D38-CATHODE)") (class "Default")
      (node (ref "D38") (pin "2") (pinfunction "CATHODE_2") (pintype "passive"))
      (node (ref "D39") (pin "1") (pinfunction "ANODE_1") (pintype "passive"))
    )
    (net (code "41") (name "Net-(D39-CATHODE)") (class "Default")
      (node (ref "D39") (pin "2") (pinfunction "CATHODE_2") (pintype "passive"))
      (node (ref "R13") (pin "1") (pinfunction "1_1") (pintype "passive"))
    )
    (net (code "42") (name "Net-(D40-CATHODE)") (class "Default")
      (node (ref "D40") (pin "2") (pinfunction "CATHODE_2") (pintype "passive"))
      (node (ref "D41") (pin "1") (pinfunction "ANODE_1") (pintype "passive"))
    )
    (net (code "43") (name "Net-(D41-CATHODE)") (class "Default")
      (node (ref "D41") (pin "2") (pinfunction "CATHODE_2") (pintype "passive"))
      (node (ref "D42") (pin "1") (pinfunction "ANODE_1") (pintype "passive"))
    )
    (net (code "44") (name "Net-(D42-CATHODE)") (class "Default")
      (node (ref "D42") (pin "2") (pinfunction "CATHODE_2") (pintype "passive"))
      (node (ref "R14") (pin "1") (pinfunction "1_1") (pintype "passive"))
    )
    (net (code "45") (name "Net-(D43-CATHODE)") (class "Default")
      (node (ref "D43") (pin "2") (pinfunction "CATHODE_2") (pintype "passive"))
      (node (ref "D44") (pin "1") (pinfunction "ANODE_1") (pintype "passive"))
    )
    (net (code "46") (name "Net-(D44-CATHODE)") (class "Default")
      (node (ref "D44") (pin "2") (pinfunction "CATHODE_2") (pintype "passive"))
      (node (ref "D45") (pin "1") (pinfunction "ANODE_1") (pintype "passive"))
    )
    (net (code "47") (name "Net-(D45-CATHODE)") (class "Default")
      (node (ref "D45") (pin "2") (pinfunction "CATHODE_2") (pintype "passive"))
      (node (ref "R15") (pin "1") (pinfunction "1_1") (pintype "passive"))
    )
    (net (code "48") (name "Net-(D46-CATHODE)") (class "Default")
      (node (ref "D46") (pin "2") (pinfunction "CATHODE_2") (pintype "passive"))
      (node (ref "D47") (pin "1") (pinfunction "ANODE_1") (pintype "passive"))
    )
    (net (code "49") (name "Net-(D47-CATHODE)") (class "Default")
      (node (ref "D47") (pin "2") (pinfunction "CATHODE_2") (pintype "passive"))
      (node (ref "D48") (pin "1") (pinfunction "ANODE_1") (pintype "passive"))
    )
    (net (code "50") (name "Net-(D48-CATHODE)") (class "Default")
      (node (ref "D48") (pin "2") (pinfunction "CATHODE_2") (pintype "passive"))
      (node (ref "R16") (pin "1") (pinfunction "1_1") (pintype "passive"))
    )
    (net (code "51") (name "Net-(D49-CATHODE)") (class "Default")
      (node (ref "D49") (pin "2") (pinfunction "CATHODE_2") (pintype "passive"))
      (node (ref "D50") (pin "1") (pinfunction "ANODE_1") (pintype "passive"))
    )
    (net (code "52") (name "Net-(D50-CATHODE)") (class "Default")
      (node (ref "D50") (pin "2") (pinfunction "CATHODE_2") (pintype "passive"))
      (node (ref "D51") (pin "1") (pinfunction "ANODE_1") (pintype "passive"))
    )
    (net (code "53") (name "Net-(D51-CATHODE)") (class "Default")
      (node (ref "D51") (pin "2") (pinfunction "CATHODE_2") (pintype "passive"))
      (node (ref "R17") (pin "1") (pinfunction "1_1") (pintype "passive"))
    )
    (net (code "54") (name "Net-(D52-CATHODE)") (class "Default")
      (node (ref "D52") (pin "2") (pinfunction "CATHODE_2") (pintype "passive"))
      (node (ref "D53") (pin "1") (pinfunction "ANODE_1") (pintype "passive"))
    )
    (net (code "55") (name "Net-(D53-CATHODE)") (class "Default")
      (node (ref "D53") (pin "2") (pinfunction "CATHODE_2") (pintype "passive"))
      (node (ref "D54") (pin "1") (pinfunction "ANODE_1") (pintype "passive"))
    )
    (net (code "56") (name "Net-(D54-CATHODE)") (class "Default")
      (node (ref "D54") (pin "2") (pinfunction "CATHODE_2") (pintype "passive"))
      (node (ref "R18") (pin "1") (pinfunction "1_1") (pintype "passive"))
    )
    (net (code "57") (name "Net-(D55-CATHODE)") (class "Default")
      (node (ref "D55") (pin "2") (pinfunction "CATHODE_2") (pintype "passive"))
      (node (ref "D56") (pin "1") (pinfunction "ANODE_1") (pintype "passive"))
    )
    (net (code "58") (name "Net-(D56-CATHODE)") (class "Default")
      (node (ref "D56") (pin "2") (pinfunction "CATHODE_2") (pintype "passive"))
      (node (ref "D57") (pin "1") (pinfunction "ANODE_1") (pintype "passive"))
    )
    (net (code "59") (name "Net-(D57-CATHODE)") (class "Default")
      (node (ref "D57") (pin "2") (pinfunction "CATHODE_2") (pintype "passive"))
      (node (ref "R19") (pin "1") (pinfunction "1_1") (pintype "passive"))
    )
    (net (code "60") (name "Net-(D58-CATHODE)") (class "Default")
      (node (ref "D58") (pin "2") (pinfunction "CATHODE_2") (pintype "passive"))
      (node (ref "D59") (pin "1") (pinfunction "ANODE_1") (pintype "passive"))
    )
    (net (code "61") (name "Net-(D59-CATHODE)") (class "Default")
      (node (ref "D59") (pin "2") (pinfunction "CATHODE_2") (pintype "passive"))
      (node (ref "D60") (pin "1") (pinfunction "ANODE_1") (pintype "passive"))
    )
    (net (code "62") (name "Net-(D60-CATHODE)") (class "Default")
      (node (ref "D60") (pin "2") (pinfunction "CATHODE_2") (pintype "passive"))
      (node (ref "R20") (pin "1") (pinfunction "1_1") (pintype "passive"))
    )
    (net (code "63") (name "Net-(D61-CATHODE)") (class "Default")
      (node (ref "D61") (pin "2") (pinfunction "CATHODE_2") (pintype "passive"))
      (node (ref "D62") (pin "1") (pinfunction "ANODE_1") (pintype "passive"))
    )
    (net (code "64") (name "Net-(D62-CATHODE)") (class "Default")
      (node (ref "D62") (pin "2") (pinfunction "CATHODE_2") (pintype "passive"))
      (node (ref "D63") (pin "1") (pinfunction "ANODE_1") (pintype "passive"))
    )
    (net (code "65") (name "Net-(D63-CATHODE)") (class "Default")
      (node (ref "D63") (pin "2") (pinfunction "CATHODE_2") (pintype "passive"))
      (node (ref "R21") (pin "1") (pinfunction "1_1") (pintype "passive"))
    )
    (net (code "66") (name "Net-(D64-CATHODE)") (class "Default")
      (node (ref "D64") (pin "2") (pinfunction "CATHODE_2") (pintype "passive"))
      (node (ref "D65") (pin "1") (pinfunction "ANODE_1") (pintype "passive"))
    )
    (net (code "67") (name "Net-(D65-CATHODE)") (class "Default")
      (node (ref "D65") (pin "2") (pinfunction "CATHODE_2") (pintype "passive"))
      (node (ref "D66") (pin "1") (pinfunction "ANODE_1") (pintype "passive"))
    )
    (net (code "68") (name "Net-(D66-CATHODE)") (class "Default")
      (node (ref "D66") (pin "2") (pinfunction "CATHODE_2") (pintype "passive"))
      (node (ref "R22") (pin "1") (pinfunction "1_1") (pintype "passive"))
    )
    (net (code "69") (name "Net-(D67-CATHODE)") (class "Default")
      (node (ref "D67") (pin "2") (pinfunction "CATHODE_2") (pintype "passive"))
      (node (ref "D68") (pin "1") (pinfunction "ANODE_1") (pintype "passive"))
    )
    (net (code "70") (name "Net-(D68-CATHODE)") (class "Default")
      (node (ref "D68") (pin "2") (pinfunction "CATHODE_2") (pintype "passive"))
      (node (ref "D69") (pin "1") (pinfunction "ANODE_1") (pintype "passive"))
    )
    (net (code "71") (name "Net-(D69-CATHODE)") (class "Default")
      (node (ref "D69") (pin "2") (pinfunction "CATHODE_2") (pintype "passive"))
      (node (ref "R23") (pin "1") (pinfunction "1_1") (pintype "passive"))
    )
    (net (code "72") (name "Net-(D70-CATHODE)") (class "Default")
      (node (ref "D70") (pin "2") (pinfunction "CATHODE_2") (pintype "passive"))
      (node (ref "D71") (pin "1") (pinfunction "ANODE_1") (pintype "passive"))
    )
    (net (code "73") (name "Net-(D71-CATHODE)") (class "Default")
      (node (ref "D71") (pin "2") (pinfunction "CATHODE_2") (pintype "passive"))
      (node (ref "D72") (pin "1") (pinfunction "ANODE_1") (pintype "passive"))
    )
    (net (code "74") (name "Net-(D72-CATHODE)") (class "Default")
      (node (ref "D72") (pin "2") (pinfunction "CATHODE_2") (pintype "passive"))
      (node (ref "R24") (pin "1") (pinfunction "1_1") (pintype "passive"))
    )
    (net (code "75") (name "Net-(D73-CATHODE)") (class "Default")
      (node (ref "D73") (pin "2") (pinfunction "CATHODE_2") (pintype "passive"))
      (node (ref "D74") (pin "1") (pinfunction "ANODE_1") (pintype "passive"))
    )
    (net (code "76") (name "Net-(D74-CATHODE)") (class "Default")
      (node (ref "D74") (pin "2") (pinfunction "CATHODE_2") (pintype "passive"))
      (node (ref "D75") (pin "1") (pinfunction "ANODE_1") (pintype "passive"))
    )
    (net (code "77") (name "Net-(D75-CATHODE)") (class "Default")
      (node (ref "D75") (pin "2") (pinfunction "CATHODE_2") (pintype "passive"))
      (node (ref "R25") (pin "1") (pinfunction "1_1") (pintype "passive"))
    )
    (net (code "78") (name "Net-(D76-CATHODE)") (class "Default")
      (node (ref "D76") (pin "2") (pinfunction "CATHODE_2") (pintype "passive"))
      (node (ref "D77") (pin "1") (pinfunction "ANODE_1") (pintype "passive"))
    )
    (net (code "79") (name "Net-(D77-CATHODE)") (class "Default")
      (node (ref "D77") (pin "2") (pinfunction "CATHODE_2") (pintype "passive"))
      (node (ref "D78") (pin "1") (pinfunction "ANODE_1") (pintype "passive"))
    )
    (net (code "80") (name "Net-(D78-CATHODE)") (class "Default")
      (node (ref "D78") (pin "2") (pinfunction "CATHODE_2") (pintype "passive"))
      (node (ref "R26") (pin "1") (pinfunction "1_1") (pintype "passive"))
    )
    (net (code "81") (name "Net-(D79-CATHODE)") (class "Default")
      (node (ref "D79") (pin "2") (pinfunction "CATHODE_2") (pintype "passive"))
      (node (ref "D80") (pin "1") (pinfunction "ANODE_1") (pintype "passive"))
    )
    (net (code "82") (name "Net-(D80-CATHODE)") (class "Default")
      (node (ref "D80") (pin "2") (pinfunction "CATHODE_2") (pintype "passive"))
      (node (ref "D81") (pin "1") (pinfunction "ANODE_1") (pintype "passive"))
    )
    (net (code "83") (name "Net-(D81-CATHODE)") (class "Default")
      (node (ref "D81") (pin "2") (pinfunction "CATHODE_2") (pintype "passive"))
      (node (ref "R27") (pin "1") (pinfunction "1_1") (pintype "passive"))
    )
    (net (code "84") (name "Net-(D82-CATHODE)") (class "Default")
      (node (ref "D82") (pin "2") (pinfunction "CATHODE_2") (pintype "passive"))
      (node (ref "D83") (pin "1") (pinfunction "ANODE_1") (pintype "passive"))
    )
    (net (code "85") (name "Net-(D83-CATHODE)") (class "Default")
      (node (ref "D83") (pin "2") (pinfunction "CATHODE_2") (pintype "passive"))
      (node (ref "D84") (pin "1") (pinfunction "ANODE_1") (pintype "passive"))
    )
    (net (code "86") (name "Net-(D84-CATHODE)") (class "Default")
      (node (ref "D84") (pin "2") (pinfunction "CATHODE_2") (pintype "passive"))
      (node (ref "R28") (pin "1") (pinfunction "1_1") (pintype "passive"))
    )
    (net (code "87") (name "Net-(D85-CATHODE)") (class "Default")
      (node (ref "D85") (pin "2") (pinfunction "CATHODE_2") (pintype "passive"))
      (node (ref "D86") (pin "1") (pinfunction "ANODE_1") (pintype "passive"))
    )
    (net (code "88") (name "Net-(D86-CATHODE)") (class "Default")
      (node (ref "D86") (pin "2") (pinfunction "CATHODE_2") (pintype "passive"))
      (node (ref "D87") (pin "1") (pinfunction "ANODE_1") (pintype "passive"))
    )
    (net (code "89") (name "Net-(D87-CATHODE)") (class "Default")
      (node (ref "D87") (pin "2") (pinfunction "CATHODE_2") (pintype "passive"))
      (node (ref "R29") (pin "1") (pinfunction "1_1") (pintype "passive"))
    )
    (net (code "90") (name "Net-(D88-CATHODE)") (class "Default")
      (node (ref "D88") (pin "2") (pinfunction "CATHODE_2") (pintype "passive"))
      (node (ref "D89") (pin "1") (pinfunction "ANODE_1") (pintype "passive"))
    )
    (net (code "91") (name "Net-(D89-CATHODE)") (class "Default")
      (node (ref "D89") (pin "2") (pinfunction "CATHODE_2") (pintype "passive"))
      (node (ref "D90") (pin "1") (pinfunction "ANODE_1") (pintype "passive"))
    )
    (net (code "92") (name "Net-(D90-CATHODE)") (class "Default")
      (node (ref "D90") (pin "2") (pinfunction "CATHODE_2") (pintype "passive"))
      (node (ref "R30") (pin "1") (pinfunction "1_1") (pintype "passive"))
    )
    (net (code "93") (name "Net-(D91-CATHODE)") (class "Default")
      (node (ref "D91") (pin "2") (pinfunction "CATHODE_2") (pintype "passive"))
      (node (ref "D92") (pin "1") (pinfunction "ANODE_1") (pintype "passive"))
    )
    (net (code "94") (name "Net-(D92-CATHODE)") (class "Default")
      (node (ref "D92") (pin "2") (pinfunction "CATHODE_2") (pintype "passive"))
      (node (ref "D93") (pin "1") (pinfunction "ANODE_1") (pintype "passive"))
    )
    (net (code "95") (name "Net-(D93-CATHODE)") (class "Default")
      (node (ref "D93") (pin "2") (pinfunction "CATHODE_2") (pintype "passive"))
      (node (ref "R31") (pin "1") (pinfunction "1_1") (pintype "passive"))
    )
    (net (code "96") (name "Net-(D94-CATHODE)") (class "Default")
      (node (ref "D94") (pin "2") (pinfunction "CATHODE_2") (pintype "passive"))
      (node (ref "D95") (pin "1") (pinfunction "ANODE_1") (pintype "passive"))
    )
    (net (code "97") (name "Net-(D95-CATHODE)") (class "Default")
      (node (ref "D95") (pin "2") (pinfunction "CATHODE_2") (pintype "passive"))
      (node (ref "D96") (pin "1") (pinfunction "ANODE_1") (pintype "passive"))
    )
    (net (code "98") (name "Net-(D96-CATHODE)") (class "Default")
      (node (ref "D96") (pin "2") (pinfunction "CATHODE_2") (pintype "passive"))
      (node (ref "R32") (pin "1") (pinfunction "1_1") (pintype "passive"))
    )
  )
)
